# LKS_074DO_0329.net
KiCad netlist of a schematic drawn in Altium Designer
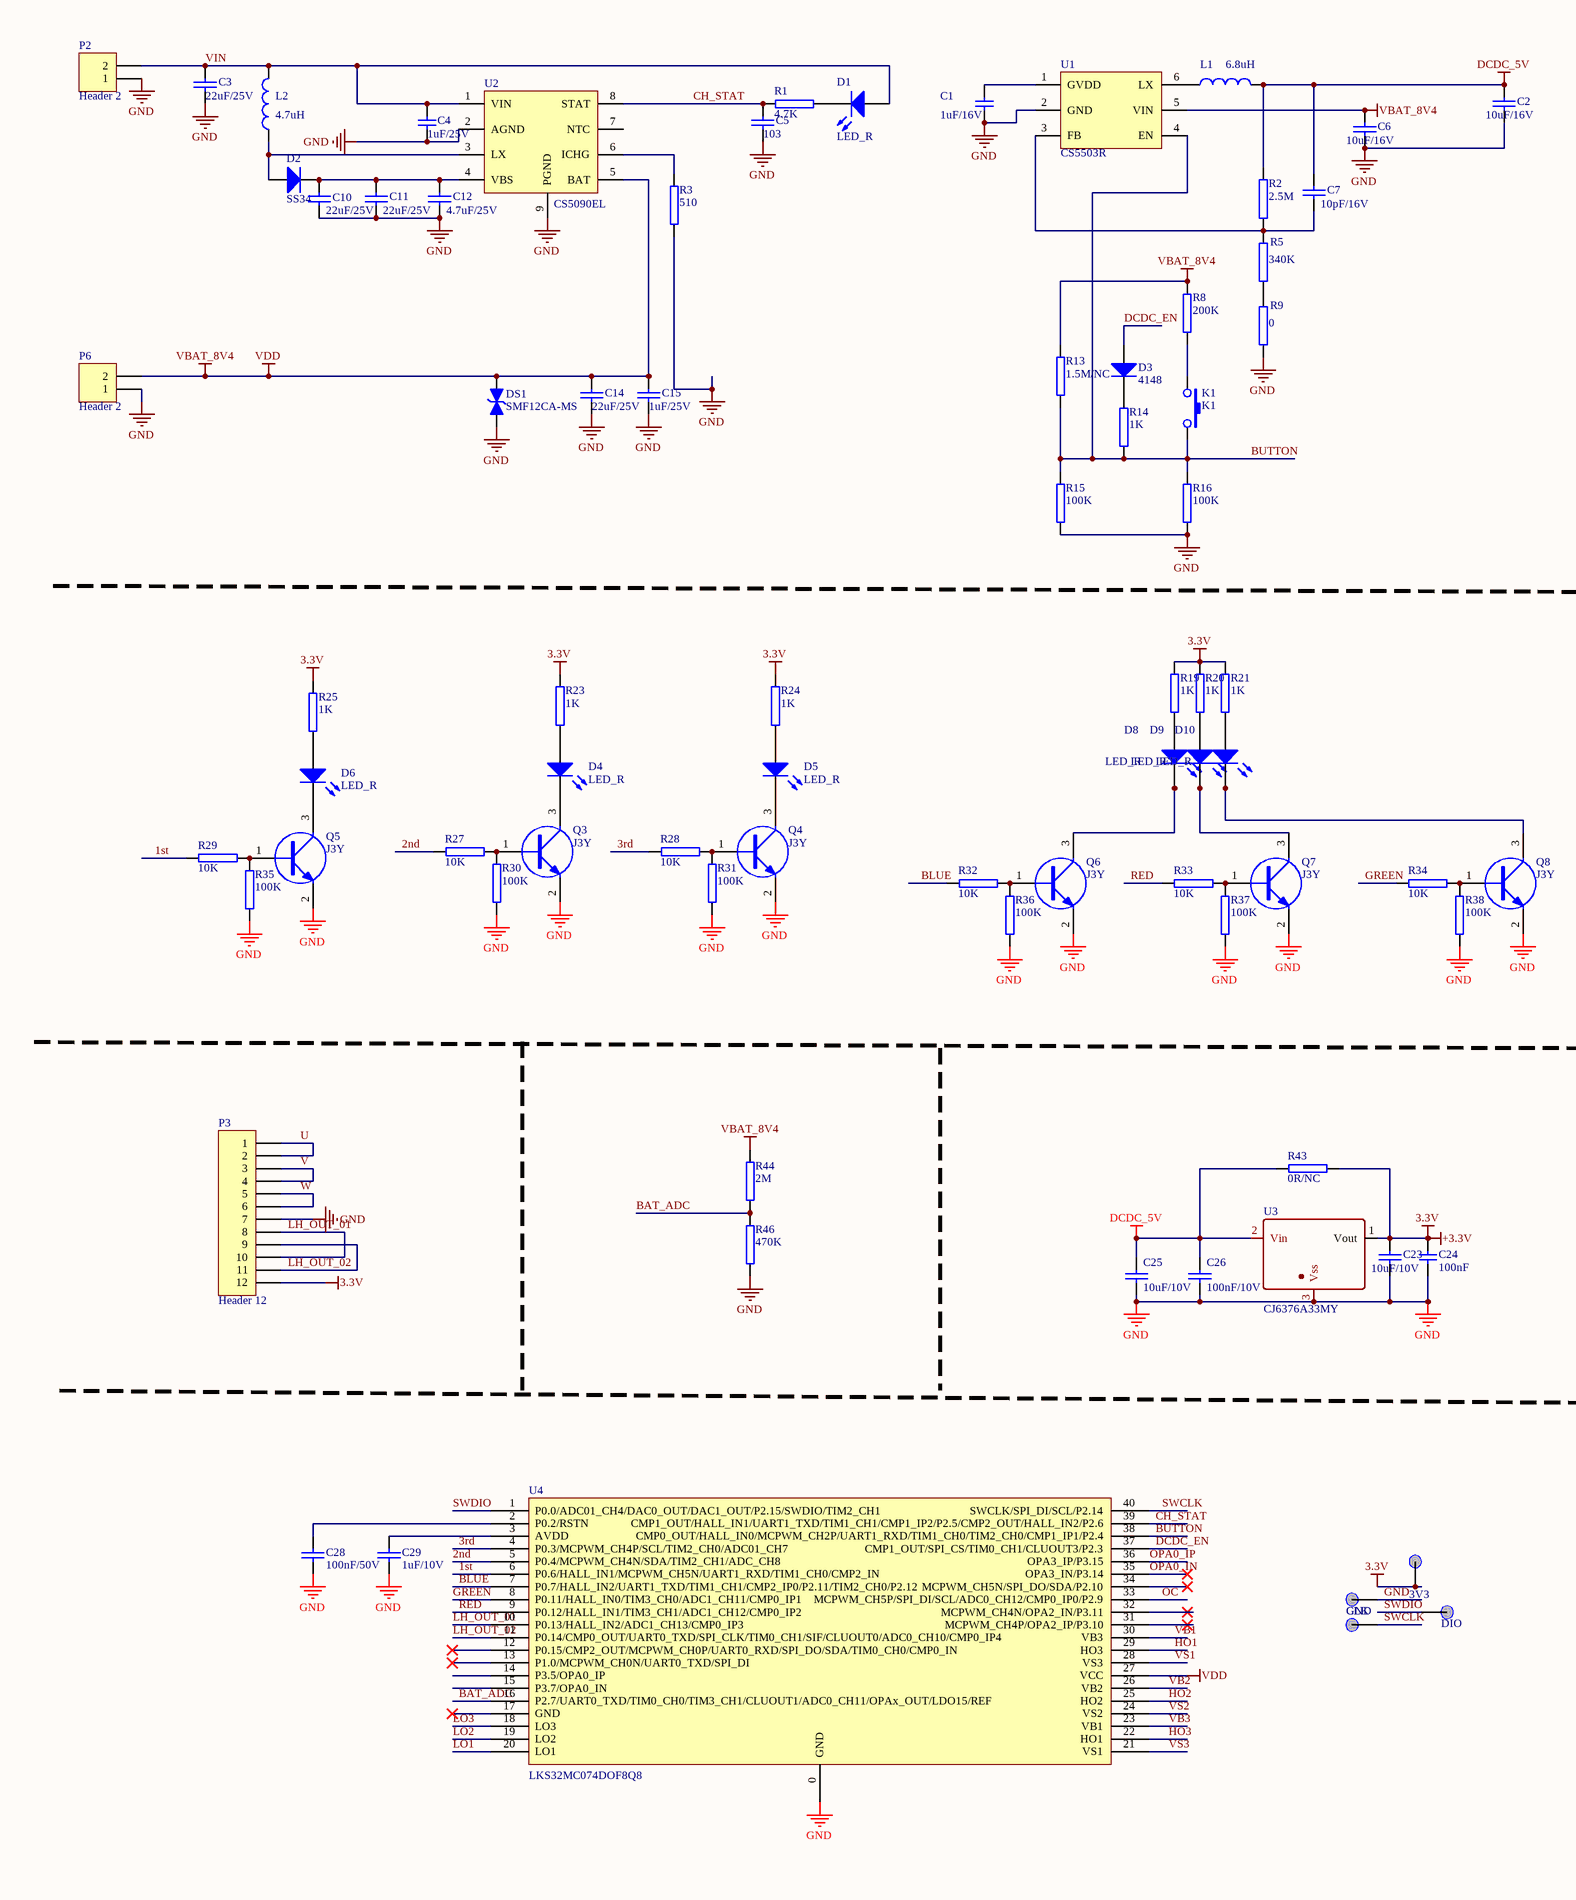
[diagram p0: LKS_074DO_0329.SchDoc, left]
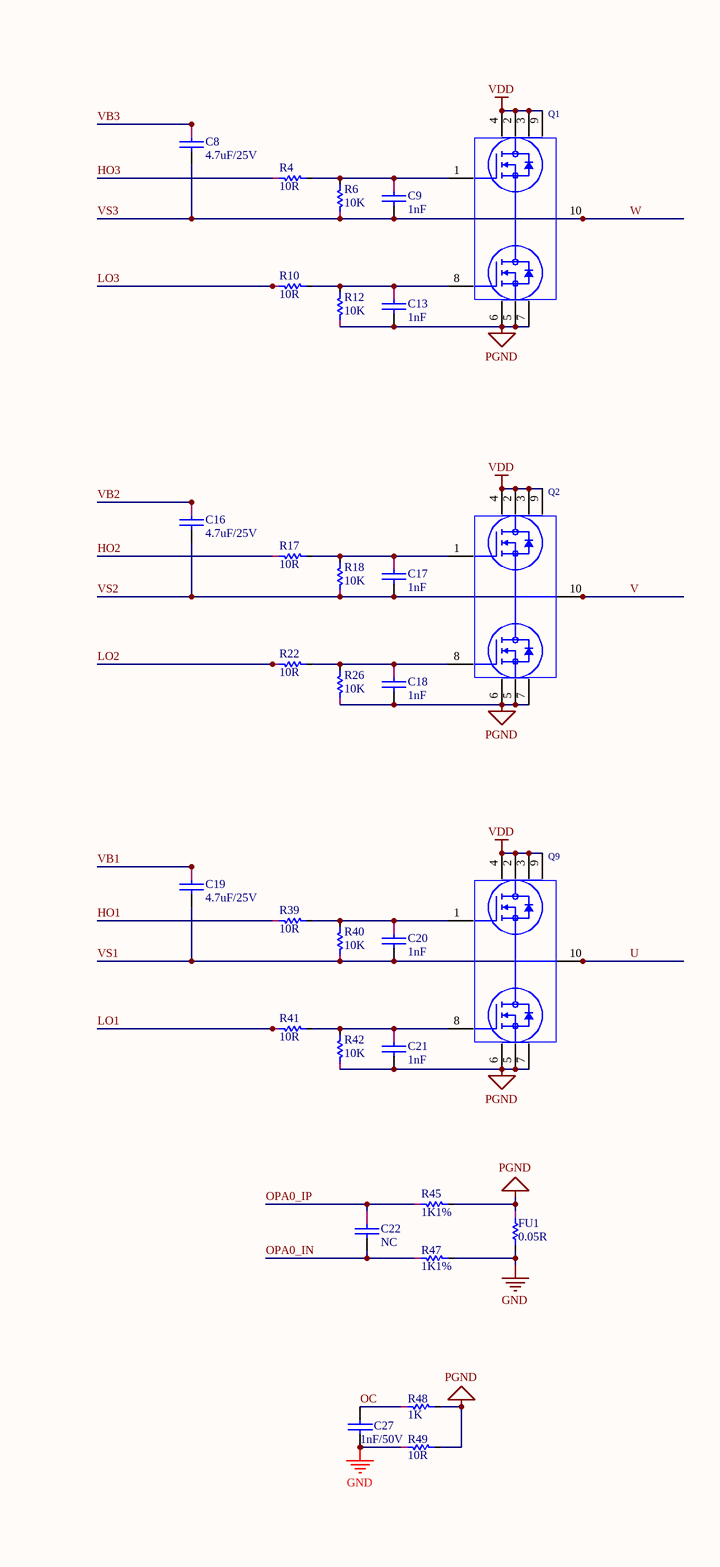
[diagram p1: LKS_074DO_0329.SchDoc, right]

(export (version "E")
  (design (tool "Eeschema 10.0.6"))
  (components
    (comp (ref "3V3") (value "test") (footprint "piot") (libsource (lib "LKS074DO_BRUSH_0329") (part "test")))
    (comp (ref "C1") (value "1uF/16V") (footprint "C 0402_M") (libsource (lib "") (part "CAP_2")))
    (comp (ref "C2")
      (value "10uF/16V")
      (footprint "C 0603_M")
      (description "Capacitor")
      (libsource (lib "*") (part "CAP"))
    )
    (comp (ref "C3")
      (value "22uF/25V")
      (footprint "C 0603_M")
      (description "Capacitor")
      (libsource (lib "*") (part "CAP"))
    )
    (comp (ref "C4") (value "1uF/25V") (footprint "C 0402_M") (libsource (lib "") (part "CAP_2")))
    (comp (ref "C5")
      (value "103")
      (footprint "R 0402_M")
      (description "Capacitor")
      (libsource (lib "*") (part "CAP"))
    )
    (comp (ref "C6")
      (value "10uF/16V")
      (footprint "C 0603_M")
      (description "Capacitor")
      (libsource (lib "*") (part "CAP"))
    )
    (comp (ref "C7")
      (value "10pF/16V")
      (footprint "C 0402_M")
      (description "Capacitor")
      (libsource (lib "*") (part "CAP"))
    )
    (comp (ref "C8")
      (value "4.7uF/25V")
      (footprint "C 0402_M")
      (description "Capacitor")
      (libsource (lib "") (part "CAP_1"))
    )
    (comp (ref "C9")
      (value "1nF")
      (footprint "C 0402_M")
      (description "Capacitor")
      (libsource (lib "") (part "CAP_1"))
    )
    (comp (ref "C10")
      (value "22uF/25V")
      (footprint "C 0603_M")
      (description "Capacitor")
      (libsource (lib "*") (part "CAP"))
    )
    (comp (ref "C11")
      (value "22uF/25V")
      (footprint "C 0603_M")
      (description "Capacitor")
      (libsource (lib "*") (part "CAP"))
    )
    (comp (ref "C12")
      (value "4.7uF/25V")
      (footprint "C 0402_M")
      (description "Capacitor")
      (libsource (lib "*") (part "CAP"))
    )
    (comp (ref "C13")
      (value "1nF")
      (footprint "C 0402_M")
      (description "Capacitor")
      (libsource (lib "") (part "CAP_1"))
    )
    (comp (ref "C14")
      (value "22uF/25V")
      (footprint "C 0603_M")
      (description "Capacitor")
      (libsource (lib "*") (part "CAP"))
    )
    (comp (ref "C15")
      (value "1uF/25V")
      (footprint "C 0402_M")
      (description "Capacitor")
      (libsource (lib "*") (part "CAP"))
    )
    (comp (ref "C16")
      (value "4.7uF/25V")
      (footprint "C 0402_M")
      (description "Capacitor")
      (libsource (lib "") (part "CAP_1"))
    )
    (comp (ref "C17")
      (value "1nF")
      (footprint "C 0402_M")
      (description "Capacitor")
      (libsource (lib "") (part "CAP_1"))
    )
    (comp (ref "C18")
      (value "1nF")
      (footprint "C 0402_M")
      (description "Capacitor")
      (libsource (lib "") (part "CAP_1"))
    )
    (comp (ref "C19")
      (value "4.7uF/25V")
      (footprint "C 0402_M")
      (description "Capacitor")
      (libsource (lib "") (part "CAP_1"))
    )
    (comp (ref "C20")
      (value "1nF")
      (footprint "C 0402_M")
      (description "Capacitor")
      (libsource (lib "") (part "CAP_1"))
    )
    (comp (ref "C21")
      (value "1nF")
      (footprint "C 0402_M")
      (description "Capacitor")
      (libsource (lib "") (part "CAP_1"))
    )
    (comp (ref "C22")
      (value "NC")
      (footprint "C 0402_M")
      (description "Capacitor")
      (libsource (lib "") (part "CAP_1"))
    )
    (comp (ref "C23")
      (value "10uF/10V")
      (footprint "C 0603_M")
      (description "Capacitor")
      (libsource (lib "*") (part "CAP"))
    )
    (comp (ref "C24") (value "100nF") (footprint "C 0402_M") (libsource (lib "") (part "CAP_2")))
    (comp (ref "C25")
      (value "10uF/10V")
      (footprint "C 0603_M")
      (description "Capacitor")
      (libsource (lib "*") (part "CAP"))
    )
    (comp (ref "C26")
      (value "100nF/10V")
      (footprint "C 0402_M")
      (description "Capacitor")
      (libsource (lib "*") (part "CAP"))
    )
    (comp (ref "C27")
      (value "1nF/50V")
      (footprint "C 0402_M")
      (description "Capacitor")
      (libsource (lib "*") (part "C"))
    )
    (comp (ref "C28")
      (value "100nF/50V")
      (footprint "C 0402_M")
      (description "Capacitor")
      (libsource (lib "*") (part "C"))
    )
    (comp (ref "C29")
      (value "1uF/10V")
      (footprint "C 0402_M")
      (description "Capacitor")
      (libsource (lib "*") (part "C"))
    )
    (comp (ref "CLK") (value "test") (footprint "piot") (libsource (lib "LKS074DO_BRUSH_0329") (part "test")))
    (comp (ref "D1") (value "LED_R") (footprint "0603-LED") (libsource (lib "PuXun1") (part "LED")))
    (comp (ref "D2")
      (value "SS34")
      (footprint "SOD123FL")
      (description "Default Diode")
      (fields (field (name "PUBLISHER") "Altium Limited"))
      (libsource (lib "LKS034DO_Motor_0520_1") (part "Diode"))
    )
    (comp (ref "D3")
      (value "4148")
      (footprint "SOD-323")
      (description "Default Diode")
      (fields (field (name "PUBLISHER") "Altium Limited"))
      (libsource (lib "LKS034DO_Motor_0520_1") (part "Diode"))
    )
    (comp (ref "D4") (value "LED_R") (footprint "0603-LED") (libsource (lib "PuXun1") (part "LED")))
    (comp (ref "D5") (value "LED_R") (footprint "0603-LED") (libsource (lib "PuXun1") (part "LED")))
    (comp (ref "D6") (value "LED_R") (footprint "0603-LED") (libsource (lib "PuXun1") (part "LED")))
    (comp (ref "D8") (value "LED_R") (footprint "0603-LED") (libsource (lib "PuXun1") (part "LED")))
    (comp (ref "D9") (value "LED_R") (footprint "0603-LED") (libsource (lib "PuXun1") (part "LED")))
    (comp (ref "D10") (value "LED_R") (footprint "0603-LED") (libsource (lib "PuXun1") (part "LED")))
    (comp (ref "DIO") (value "test") (footprint "piot") (libsource (lib "LKS074DO_BRUSH_0329") (part "test")))
    (comp (ref "DS1")
      (value "SMF12CA-MS")
      (footprint "SOD-123F")
      (description "12V/19.9V")
      (libsource (lib "*") (part "DIODE-3"))
    )
    (comp (ref "FU1") (value "0.05R") (footprint "R 0805_M") (libsource (lib "*") (part "RAS")))
    (comp (ref "GND") (value "test") (footprint "piot") (libsource (lib "LKS074DO_BRUSH_0329") (part "test")))
    (comp (ref "K1") (value "K1") (footprint "SMD3.3X3.3X2") (libsource (lib "SCHLIB_NEW") (part "K1")))
    (comp (ref "L1")
      (value "6.8uH")
      (footprint "SMD3.5X3 .2- duplicate")
      (description "Inductor")
      (fields (field (name "PUBLISHER") "Altium Limited"))
      (libsource (lib "Miscellaneous Devices") (part "Inductor"))
    )
    (comp (ref "L2")
      (value "4.7uH")
      (footprint "SMD3.5X3 .2- duplicate")
      (description "Inductor")
      (fields (field (name "PUBLISHER") "Altium Limited"))
      (libsource (lib "Miscellaneous Devices") (part "Inductor"))
    )
    (comp (ref "P2")
      (value "Header 2")
      (footprint "CONN_SMD_2P_0.6")
      (description "Header, 2-Pin")
      (fields (field (name "PUBLISHER") "Altium Limited"))
      (libsource (lib "Miscellaneous Connectors") (part "Header 2"))
    )
    (comp (ref "P3")
      (value "Header 12")
      (footprint "SMD-12")
      (description "Header, 12-Pin")
      (fields (field (name "PUBLISHER") "Altium Limited"))
      (libsource (lib "Miscellaneous Connectors") (part "Header 12"))
    )
    (comp (ref "P6")
      (value "Header 2")
      (footprint "CONN_SMD_2P_0.6")
      (description "Header, 2-Pin")
      (fields (field (name "PUBLISHER") "Altium Limited"))
      (libsource (lib "Miscellaneous Connectors") (part "Header 2"))
    )
    (comp (ref "Q1") (value "CJBM3020") (footprint "DFN-3X3_8") (libsource (lib "*") (part "CJBM3020")))
    (comp (ref "Q2") (value "CJBM3020") (footprint "DFN-3X3_8") (libsource (lib "*") (part "CJBM3020")))
    (comp (ref "Q3")
      (value "J3Y")
      (footprint "SOT-23")
      (description "NPN Transistor")
      (libsource (lib "*") (part "NPN"))
    )
    (comp (ref "Q4")
      (value "J3Y")
      (footprint "SOT-23")
      (description "NPN Transistor")
      (libsource (lib "*") (part "NPN"))
    )
    (comp (ref "Q5")
      (value "J3Y")
      (footprint "SOT-23")
      (description "NPN Transistor")
      (libsource (lib "*") (part "NPN"))
    )
    (comp (ref "Q6")
      (value "J3Y")
      (footprint "SOT-23")
      (description "NPN Transistor")
      (libsource (lib "*") (part "NPN"))
    )
    (comp (ref "Q7")
      (value "J3Y")
      (footprint "SOT-23")
      (description "NPN Transistor")
      (libsource (lib "*") (part "NPN"))
    )
    (comp (ref "Q8")
      (value "J3Y")
      (footprint "SOT-23")
      (description "NPN Transistor")
      (libsource (lib "*") (part "NPN"))
    )
    (comp (ref "Q9") (value "CJBM3020") (footprint "DFN-3X3_8") (libsource (lib "*") (part "CJBM3020")))
    (comp (ref "R1") (value "4.7K") (footprint "C 0402_M") (libsource (lib "*") (part "RES2_S")))
    (comp (ref "R2") (value "2.5M") (footprint "C 0402_M") (libsource (lib "*") (part "RES2_S")))
    (comp (ref "R3") (value "510") (footprint "R 0402_M") (libsource (lib "*") (part "RES2_S")))
    (comp (ref "R4") (value "10R") (footprint "R 0402_M") (libsource (lib "*") (part "RAS")))
    (comp (ref "R5") (value "340K") (footprint "C 0402_M") (libsource (lib "*") (part "RES2_S")))
    (comp (ref "R6") (value "10K") (footprint "R 0402_M") (libsource (lib "*") (part "RAS")))
    (comp (ref "R8") (value "200K") (footprint "C 0402_M") (libsource (lib "*") (part "RES2_S")))
    (comp (ref "R9") (value "0") (footprint "C 0402_M") (libsource (lib "*") (part "RES2_S")))
    (comp (ref "R10") (value "10R") (footprint "R 0402_M") (libsource (lib "*") (part "RAS")))
    (comp (ref "R12") (value "10K") (footprint "R 0402_M") (libsource (lib "*") (part "RAS")))
    (comp (ref "R13") (value "1.5M/NC") (footprint "C 0402_M") (libsource (lib "*") (part "RES2_S")))
    (comp (ref "R14") (value "1K") (footprint "C 0402_M") (libsource (lib "*") (part "RES2_S")))
    (comp (ref "R15") (value "100K") (footprint "C 0402_M") (libsource (lib "*") (part "RES2_S")))
    (comp (ref "R16") (value "100K") (footprint "C 0402_M") (libsource (lib "*") (part "RES2_S")))
    (comp (ref "R17") (value "10R") (footprint "R 0402_M") (libsource (lib "*") (part "RAS")))
    (comp (ref "R18") (value "10K") (footprint "R 0402_M") (libsource (lib "*") (part "RAS")))
    (comp (ref "R19") (value "1K") (footprint "C 0402_M") (libsource (lib "*") (part "RES2_S")))
    (comp (ref "R20") (value "1K") (footprint "C 0402_M") (libsource (lib "*") (part "RES2_S")))
    (comp (ref "R21") (value "1K") (footprint "C 0402_M") (libsource (lib "*") (part "RES2_S")))
    (comp (ref "R22") (value "10R") (footprint "R 0402_M") (libsource (lib "*") (part "RAS")))
    (comp (ref "R23") (value "1K") (footprint "C 0402_M") (libsource (lib "*") (part "RES2_S")))
    (comp (ref "R24") (value "1K") (footprint "C 0402_M") (libsource (lib "*") (part "RES2_S")))
    (comp (ref "R25") (value "1K") (footprint "C 0402_M") (libsource (lib "*") (part "RES2_S")))
    (comp (ref "R26") (value "10K") (footprint "R 0402_M") (libsource (lib "*") (part "RAS")))
    (comp (ref "R27") (value "10K") (footprint "C 0402_M") (libsource (lib "*") (part "RES2_S")))
    (comp (ref "R28") (value "10K") (footprint "C 0402_M") (libsource (lib "*") (part "RES2_S")))
    (comp (ref "R29") (value "10K") (footprint "C 0402_M") (libsource (lib "*") (part "RES2_S")))
    (comp (ref "R30") (value "100K") (footprint "C 0402_M") (libsource (lib "*") (part "RES2_S")))
    (comp (ref "R31") (value "100K") (footprint "C 0402_M") (libsource (lib "*") (part "RES2_S")))
    (comp (ref "R32") (value "10K") (footprint "C 0402_M") (libsource (lib "*") (part "RES2_S")))
    (comp (ref "R33") (value "10K") (footprint "C 0402_M") (libsource (lib "*") (part "RES2_S")))
    (comp (ref "R34") (value "10K") (footprint "C 0402_M") (libsource (lib "*") (part "RES2_S")))
    (comp (ref "R35") (value "100K") (footprint "C 0402_M") (libsource (lib "*") (part "RES2_S")))
    (comp (ref "R36") (value "100K") (footprint "C 0402_M") (libsource (lib "*") (part "RES2_S")))
    (comp (ref "R37") (value "100K") (footprint "C 0402_M") (libsource (lib "*") (part "RES2_S")))
    (comp (ref "R38") (value "100K") (footprint "C 0402_M") (libsource (lib "*") (part "RES2_S")))
    (comp (ref "R39") (value "10R") (footprint "R 0402_M") (libsource (lib "*") (part "RAS")))
    (comp (ref "R40") (value "10K") (footprint "R 0402_M") (libsource (lib "*") (part "RAS")))
    (comp (ref "R41") (value "10R") (footprint "R 0402_M") (libsource (lib "*") (part "RAS")))
    (comp (ref "R42") (value "10K") (footprint "R 0402_M") (libsource (lib "*") (part "RAS")))
    (comp (ref "R43") (value "0R/NC") (footprint "0603") (libsource (lib "*") (part "RES2_S")))
    (comp (ref "R44") (value "2M") (footprint "C 0402_M") (libsource (lib "*") (part "RES2_S")))
    (comp (ref "R45") (value "1K1%") (footprint "R 0402_M") (libsource (lib "*") (part "RAS")))
    (comp (ref "R46") (value "470K") (footprint "C 0402_M") (libsource (lib "*") (part "RES2_S")))
    (comp (ref "R47") (value "1K1%") (footprint "R 0402_M") (libsource (lib "*") (part "RAS")))
    (comp (ref "R48") (value "1K") (footprint "R 0402_M") (libsource (lib "*") (part "RAS")))
    (comp (ref "R49") (value "10R") (footprint "R 0402_M") (libsource (lib "*") (part "RAS")))
    (comp (ref "U1")
      (value "CS5503R")
      (footprint "SOT23-6L")
      (libsource (lib "LKS034DO_Motor_0520_1") (part "CS5503R"))
    )
    (comp (ref "U2")
      (value "CS5090EL")
      (footprint "DFN2X2_8_0.5")
      (libsource (lib "LKS034DO_Motor_0520_1") (part "CS5090EL"))
    )
    (comp (ref "U3")
      (value "CJ6376A33MY")
      (footprint "SOT-23")
      (libsource (lib "LKS034DO_Motor_0520_1") (part "78L15"))
    )
    (comp (ref "U4")
      (value "LKS32MC074DOF8Q8")
      (footprint "QFN40")
      (description "芯片")
      (libsource (lib "Q_LINKO_V1.0") (part "LKS32MC074DF8Q8"))
    )
  )
  (nets
    (net (code "1") (name "+3.3V") (class "Default")
      (node (ref "3V3") (pin "1") (pinfunction "1_1") (pintype "passive"))
      (node (ref "C23") (pin "2") (pinfunction "2_2") (pintype "passive"))
      (node (ref "C24") (pin "1") (pinfunction "1_1") (pintype "passive"))
      (node (ref "P3") (pin "12") (pinfunction "12_12") (pintype "passive"))
      (node (ref "R19") (pin "2") (pinfunction "2_2") (pintype "passive"))
      (node (ref "R20") (pin "2") (pinfunction "2_2") (pintype "passive"))
      (node (ref "R21") (pin "2") (pinfunction "2_2") (pintype "passive"))
      (node (ref "R23") (pin "2") (pinfunction "2_2") (pintype "passive"))
      (node (ref "R24") (pin "2") (pinfunction "2_2") (pintype "passive"))
      (node (ref "R25") (pin "2") (pinfunction "2_2") (pintype "passive"))
      (node (ref "R43") (pin "2") (pinfunction "2_2") (pintype "passive"))
      (node (ref "U3") (pin "1") (pinfunction "Vout_1") (pintype "passive"))
    )
    (net (code "2") (name "/1st") (class "Default")
      (node (ref "R29") (pin "2") (pinfunction "2_2") (pintype "passive"))
      (node (ref "U4") (pin "6") (pinfunction "P0.6/HALL_IN1/MCPWM_CH5N/UART1_RXD/TIM1_CH0/CMP2_IN_6") (pintype "passive"))
    )
    (net (code "3") (name "/2nd") (class "Default")
      (node (ref "R27") (pin "2") (pinfunction "2_2") (pintype "passive"))
      (node (ref "U4") (pin "5") (pinfunction "P0.4/MCPWM_CH4N/SDA/TIM2_CH1/ADC_CH8_5") (pintype "passive"))
    )
    (net (code "4") (name "/3rd") (class "Default")
      (node (ref "R28") (pin "2") (pinfunction "2_2") (pintype "passive"))
      (node (ref "U4") (pin "4") (pinfunction "P0.3/MCPWM_CH4P/SCL/TIM2_CH0/ADC01_CH7_4") (pintype "passive"))
    )
    (net (code "5") (name "/BAT_ADC") (class "Default")
      (node (ref "R44") (pin "2") (pinfunction "2_2") (pintype "passive"))
      (node (ref "R46") (pin "1") (pinfunction "1_1") (pintype "passive"))
      (node (ref "U4") (pin "16") (pinfunction "P2.7/UART0_TXD/TIM0_CH0/TIM3_CH1/CLUOUT1/ADC0_CH11/OPAx_OUT/LDO15/REF_16") (pintype "passive"))
    )
    (net (code "6") (name "/BLUE") (class "Default")
      (node (ref "R32") (pin "2") (pinfunction "2_2") (pintype "passive"))
      (node (ref "U4") (pin "7") (pinfunction "P0.7/HALL_IN2/UART1_TXD/TIM1_CH1/CMP2_IP0/P2.11/TIM2_CH0/P2.12_7") (pintype "passive"))
    )
    (net (code "7") (name "/BUTTON") (class "Default")
      (node (ref "K1") (pin "2") (pintype "passive"))
      (node (ref "R13") (pin "2") (pinfunction "2_2") (pintype "passive"))
      (node (ref "R14") (pin "2") (pinfunction "2_2") (pintype "passive"))
      (node (ref "R15") (pin "2") (pinfunction "2_2") (pintype "passive"))
      (node (ref "R16") (pin "1") (pinfunction "1_1") (pintype "passive"))
      (node (ref "U1") (pin "4") (pinfunction "EN_4") (pintype "passive"))
      (node (ref "U4") (pin "38") (pinfunction "CMP0_OUT/HALL_IN0/MCPWM_CH2P/UART1_RXD/TIM1_CH0/TIM2_CH0/CMP1_IP1/P2.4_38") (pintype "passive"))
    )
    (net (code "8") (name "/CH_STAT") (class "Default")
      (node (ref "C5") (pin "2") (pinfunction "2_2") (pintype "passive"))
      (node (ref "R1") (pin "1") (pinfunction "1_1") (pintype "passive"))
      (node (ref "U2") (pin "8") (pinfunction "STAT_8") (pintype "passive"))
      (node (ref "U4") (pin "39") (pinfunction "CMP1_OUT/HALL_IN1/UART1_TXD/TIM1_CH1/CMP1_IP2/P2.5/CMP2_OUT/HALL_IN2/P2.6_39") (pintype "passive"))
    )
    (net (code "9") (name "/DCDC_EN") (class "Default")
      (node (ref "D3") (pin "1") (pinfunction "A_1") (pintype "passive"))
      (node (ref "U4") (pin "37") (pinfunction "CMP1_OUT/SPI_CS/TIM0_CH1/CLUOUT3/P2.3_37") (pintype "passive"))
    )
    (net (code "10") (name "/GREEN") (class "Default")
      (node (ref "R34") (pin "2") (pinfunction "2_2") (pintype "passive"))
      (node (ref "U4") (pin "8") (pinfunction "P0.11/HALL_IN0/TIM3_CH0/ADC1_CH11/CMP0_IP1_8") (pintype "passive"))
    )
    (net (code "11") (name "/HO1") (class "Default")
      (node (ref "R39") (pin "2") (pinfunction "2_2") (pintype "passive"))
      (node (ref "U4") (pin "29") (pinfunction "HO3_29") (pintype "passive"))
    )
    (net (code "12") (name "/HO2") (class "Default")
      (node (ref "R17") (pin "2") (pinfunction "2_2") (pintype "passive"))
      (node (ref "U4") (pin "25") (pinfunction "HO2_25") (pintype "passive"))
    )
    (net (code "13") (name "/HO3") (class "Default")
      (node (ref "R4") (pin "2") (pinfunction "2_2") (pintype "passive"))
      (node (ref "U4") (pin "22") (pinfunction "HO1_22") (pintype "passive"))
    )
    (net (code "14") (name "/LH_OUT_01") (class "Default")
      (node (ref "P3") (pin "10") (pinfunction "10_10") (pintype "passive"))
      (node (ref "P3") (pin "8") (pinfunction "8_8") (pintype "passive"))
      (node (ref "U4") (pin "10") (pinfunction "P0.13/HALL_IN2/ADC1_CH13/CMP0_IP3_10") (pintype "passive"))
    )
    (net (code "15") (name "/LH_OUT_02") (class "Default")
      (node (ref "P3") (pin "11") (pinfunction "11_11") (pintype "passive"))
      (node (ref "P3") (pin "9") (pinfunction "9_9") (pintype "passive"))
      (node (ref "U4") (pin "11") (pinfunction "P0.14/CMP0_OUT/UART0_TXD/SPI_CLK/TIM0_CH1/SIF/CLUOUT0/ADC0_CH10/CMP0_IP4_11") (pintype "passive"))
    )
    (net (code "16") (name "/LO1") (class "Default")
      (node (ref "R41") (pin "2") (pinfunction "2_2") (pintype "passive"))
      (node (ref "U4") (pin "20") (pinfunction "LO1_20") (pintype "passive"))
    )
    (net (code "17") (name "/LO2") (class "Default")
      (node (ref "R22") (pin "2") (pinfunction "2_2") (pintype "passive"))
      (node (ref "U4") (pin "19") (pinfunction "LO2_19") (pintype "passive"))
    )
    (net (code "18") (name "/LO3") (class "Default")
      (node (ref "R10") (pin "2") (pinfunction "2_2") (pintype "passive"))
      (node (ref "U4") (pin "18") (pinfunction "LO3_18") (pintype "passive"))
    )
    (net (code "19") (name "/OC") (class "Default")
      (node (ref "C27") (pin "2") (pinfunction "2_2") (pintype "passive"))
      (node (ref "R48") (pin "2") (pinfunction "2_2") (pintype "passive"))
      (node (ref "U4") (pin "33") (pinfunction "MCPWM_CH5P/SPI_DI/SCL/ADC0_CH12/CMP0_IP0/P2.9_33") (pintype "passive"))
    )
    (net (code "20") (name "/OPA0_IN") (class "Default")
      (node (ref "C22") (pin "1") (pinfunction "1_1") (pintype "passive"))
      (node (ref "R47") (pin "2") (pinfunction "2_2") (pintype "passive"))
      (node (ref "U4") (pin "35") (pinfunction "OPA3_IN/P3.14_35") (pintype "passive"))
    )
    (net (code "21") (name "/OPA0_IP") (class "Default")
      (node (ref "C22") (pin "2") (pinfunction "2_2") (pintype "passive"))
      (node (ref "R45") (pin "2") (pinfunction "2_2") (pintype "passive"))
      (node (ref "U4") (pin "36") (pinfunction "OPA3_IP/P3.15_36") (pintype "passive"))
    )
    (net (code "22") (name "/RED") (class "Default")
      (node (ref "R33") (pin "2") (pinfunction "2_2") (pintype "passive"))
      (node (ref "U4") (pin "9") (pinfunction "P0.12/HALL_IN1/TIM3_CH1/ADC1_CH12/CMP0_IP2_9") (pintype "passive"))
    )
    (net (code "23") (name "/SWCLK") (class "Default")
      (node (ref "CLK") (pin "1") (pinfunction "1_1") (pintype "passive"))
      (node (ref "U4") (pin "40") (pinfunction "SWCLK/SPI_DI/SCL/P2.14_40") (pintype "passive"))
    )
    (net (code "24") (name "/SWDIO") (class "Default")
      (node (ref "DIO") (pin "1") (pinfunction "1_1") (pintype "passive"))
      (node (ref "U4") (pin "1") (pinfunction "P0.0/ADC01_CH4/DAC0_OUT/DAC1_OUT/P2.15/SWDIO/TIM2_CH1_1") (pintype "passive"))
    )
    (net (code "25") (name "/U") (class "Default")
      (node (ref "C19") (pin "1") (pinfunction "1_1") (pintype "passive"))
      (node (ref "C20") (pin "1") (pinfunction "1_1") (pintype "passive"))
      (node (ref "P3") (pin "1") (pinfunction "1_1") (pintype "passive"))
      (node (ref "P3") (pin "2") (pinfunction "2_2") (pintype "passive"))
      (node (ref "Q9") (pin "10") (pinfunction "S1/D2_10") (pintype "passive"))
      (node (ref "R40") (pin "2") (pinfunction "2_2") (pintype "passive"))
      (node (ref "U4") (pin "28") (pinfunction "VS3_28") (pintype "passive"))
    )
    (net (code "26") (name "/V") (class "Default")
      (node (ref "C16") (pin "1") (pinfunction "1_1") (pintype "passive"))
      (node (ref "C17") (pin "1") (pinfunction "1_1") (pintype "passive"))
      (node (ref "P3") (pin "3") (pinfunction "3_3") (pintype "passive"))
      (node (ref "P3") (pin "4") (pinfunction "4_4") (pintype "passive"))
      (node (ref "Q2") (pin "10") (pinfunction "S1/D2_10") (pintype "passive"))
      (node (ref "R18") (pin "2") (pinfunction "2_2") (pintype "passive"))
      (node (ref "U4") (pin "24") (pinfunction "VS2_24") (pintype "passive"))
    )
    (net (code "27") (name "/VB1") (class "Default")
      (node (ref "C19") (pin "2") (pinfunction "2_2") (pintype "passive"))
      (node (ref "U4") (pin "30") (pinfunction "VB3_30") (pintype "passive"))
    )
    (net (code "28") (name "/VB2") (class "Default")
      (node (ref "C16") (pin "2") (pinfunction "2_2") (pintype "passive"))
      (node (ref "U4") (pin "26") (pinfunction "VB2_26") (pintype "passive"))
    )
    (net (code "29") (name "/VB3") (class "Default")
      (node (ref "C8") (pin "2") (pinfunction "2_2") (pintype "passive"))
      (node (ref "U4") (pin "23") (pinfunction "VB1_23") (pintype "passive"))
    )
    (net (code "30") (name "/VIN") (class "Default")
      (node (ref "C3") (pin "2") (pinfunction "2_2") (pintype "passive"))
      (node (ref "C4") (pin "1") (pinfunction "1_1") (pintype "passive"))
      (node (ref "D1") (pin "1") (pinfunction "A_1") (pintype "passive"))
      (node (ref "L2") (pin "2") (pinfunction "2_2") (pintype "passive"))
      (node (ref "P2") (pin "2") (pinfunction "2_2") (pintype "passive"))
      (node (ref "U2") (pin "1") (pinfunction "VIN_1") (pintype "passive"))
    )
    (net (code "31") (name "/VS3") (class "Default")
      (node (ref "C8") (pin "1") (pinfunction "1_1") (pintype "passive"))
      (node (ref "C9") (pin "1") (pinfunction "1_1") (pintype "passive"))
      (node (ref "P3") (pin "5") (pinfunction "5_5") (pintype "passive"))
      (node (ref "P3") (pin "6") (pinfunction "6_6") (pintype "passive"))
      (node (ref "Q1") (pin "10") (pinfunction "S1/D2_10") (pintype "passive"))
      (node (ref "R6") (pin "2") (pinfunction "2_2") (pintype "passive"))
      (node (ref "U4") (pin "21") (pinfunction "VS1_21") (pintype "passive"))
    )
    (net (code "32") (name "DCDC_5V") (class "Default")
      (node (ref "C2") (pin "2") (pinfunction "2_2") (pintype "passive"))
      (node (ref "C25") (pin "2") (pinfunction "2_2") (pintype "passive"))
      (node (ref "C26") (pin "1") (pinfunction "1_1") (pintype "passive"))
      (node (ref "C7") (pin "2") (pinfunction "2_2") (pintype "passive"))
      (node (ref "L1") (pin "2") (pinfunction "2_2") (pintype "passive"))
      (node (ref "R2") (pin "1") (pinfunction "1_1") (pintype "passive"))
      (node (ref "R43") (pin "1") (pinfunction "1_1") (pintype "passive"))
      (node (ref "U3") (pin "2") (pinfunction "Vin_2") (pintype "passive"))
    )
    (net (code "33") (name "GND") (class "Default")
      (node (ref "C1") (pin "1") (pinfunction "1_1") (pintype "passive"))
      (node (ref "C10") (pin "1") (pinfunction "1_1") (pintype "passive"))
      (node (ref "C11") (pin "1") (pinfunction "1_1") (pintype "passive"))
      (node (ref "C12") (pin "1") (pinfunction "1_1") (pintype "passive"))
      (node (ref "C14") (pin "1") (pinfunction "1_1") (pintype "passive"))
      (node (ref "C15") (pin "1") (pinfunction "1_1") (pintype "passive"))
      (node (ref "C2") (pin "1") (pinfunction "1_1") (pintype "passive"))
      (node (ref "C23") (pin "1") (pinfunction "1_1") (pintype "passive"))
      (node (ref "C24") (pin "2") (pinfunction "2_2") (pintype "passive"))
      (node (ref "C25") (pin "1") (pinfunction "1_1") (pintype "passive"))
      (node (ref "C26") (pin "2") (pinfunction "2_2") (pintype "passive"))
      (node (ref "C27") (pin "1") (pinfunction "1_1") (pintype "passive"))
      (node (ref "C28") (pin "2") (pinfunction "2_2") (pintype "passive"))
      (node (ref "C29") (pin "1") (pinfunction "1_1") (pintype "passive"))
      (node (ref "C3") (pin "1") (pinfunction "1_1") (pintype "passive"))
      (node (ref "C4") (pin "2") (pinfunction "2_2") (pintype "passive"))
      (node (ref "C5") (pin "1") (pinfunction "1_1") (pintype "passive"))
      (node (ref "C6") (pin "1") (pinfunction "1_1") (pintype "passive"))
      (node (ref "DS1") (pin "2") (pinfunction "K_2") (pintype "passive"))
      (node (ref "FU1") (pin "1") (pinfunction "1_1") (pintype "passive"))
      (node (ref "GND") (pin "1") (pinfunction "1_1") (pintype "passive"))
      (node (ref "P2") (pin "1") (pinfunction "1_1") (pintype "passive"))
      (node (ref "P3") (pin "7") (pinfunction "7_7") (pintype "passive"))
      (node (ref "P6") (pin "1") (pinfunction "1_1") (pintype "passive"))
      (node (ref "Q3") (pin "2") (pinfunction "E_2") (pintype "passive"))
      (node (ref "Q4") (pin "2") (pinfunction "E_2") (pintype "passive"))
      (node (ref "Q5") (pin "2") (pinfunction "E_2") (pintype "passive"))
      (node (ref "Q6") (pin "2") (pinfunction "E_2") (pintype "passive"))
      (node (ref "Q7") (pin "2") (pinfunction "E_2") (pintype "passive"))
      (node (ref "Q8") (pin "2") (pinfunction "E_2") (pintype "passive"))
      (node (ref "R15") (pin "1") (pinfunction "1_1") (pintype "passive"))
      (node (ref "R16") (pin "2") (pinfunction "2_2") (pintype "passive"))
      (node (ref "R3") (pin "2") (pinfunction "2_2") (pintype "passive"))
      (node (ref "R30") (pin "2") (pinfunction "2_2") (pintype "passive"))
      (node (ref "R31") (pin "2") (pinfunction "2_2") (pintype "passive"))
      (node (ref "R35") (pin "2") (pinfunction "2_2") (pintype "passive"))
      (node (ref "R36") (pin "2") (pinfunction "2_2") (pintype "passive"))
      (node (ref "R37") (pin "2") (pinfunction "2_2") (pintype "passive"))
      (node (ref "R38") (pin "2") (pinfunction "2_2") (pintype "passive"))
      (node (ref "R46") (pin "2") (pinfunction "2_2") (pintype "passive"))
      (node (ref "R47") (pin "1") (pinfunction "1_1") (pintype "passive"))
      (node (ref "R49") (pin "2") (pinfunction "2_2") (pintype "passive"))
      (node (ref "R9") (pin "2") (pinfunction "2_2") (pintype "passive"))
      (node (ref "U1") (pin "2") (pinfunction "GND_2") (pintype "passive"))
      (node (ref "U2") (pin "2") (pinfunction "AGND_2") (pintype "passive"))
      (node (ref "U2") (pin "9") (pinfunction "PGND_9") (pintype "passive"))
      (node (ref "U3") (pin "3") (pinfunction "Vss_3") (pintype "passive"))
      (node (ref "U4") (pin "0") (pinfunction "GND_0") (pintype "passive"))
    )
    (net (code "34") (name "Net-(D1-K)") (class "Default")
      (node (ref "D1") (pin "2") (pinfunction "K_2") (pintype "passive"))
      (node (ref "R1") (pin "2") (pinfunction "2_2") (pintype "passive"))
    )
    (net (code "35") (name "Net-(D2-A)") (class "Default")
      (node (ref "D2") (pin "1") (pinfunction "A_1") (pintype "passive"))
      (node (ref "L2") (pin "1") (pinfunction "1_1") (pintype "passive"))
      (node (ref "U2") (pin "3") (pinfunction "LX_3") (pintype "passive"))
    )
    (net (code "36") (name "Net-(D2-K)") (class "Default")
      (node (ref "C10") (pin "2") (pinfunction "2_2") (pintype "passive"))
      (node (ref "C11") (pin "2") (pinfunction "2_2") (pintype "passive"))
      (node (ref "C12") (pin "2") (pinfunction "2_2") (pintype "passive"))
      (node (ref "D2") (pin "2") (pinfunction "K_2") (pintype "passive"))
      (node (ref "U2") (pin "4") (pinfunction "VBS_4") (pintype "passive"))
    )
    (net (code "37") (name "Net-(D3-K)") (class "Default")
      (node (ref "D3") (pin "2") (pinfunction "K_2") (pintype "passive"))
      (node (ref "R14") (pin "1") (pinfunction "1_1") (pintype "passive"))
    )
    (net (code "38") (name "Net-(D4-A)") (class "Default")
      (node (ref "D4") (pin "1") (pinfunction "A_1") (pintype "passive"))
      (node (ref "R23") (pin "1") (pinfunction "1_1") (pintype "passive"))
    )
    (net (code "39") (name "Net-(D4-K)") (class "Default")
      (node (ref "D4") (pin "2") (pinfunction "K_2") (pintype "passive"))
      (node (ref "Q3") (pin "3") (pinfunction "C_3") (pintype "passive"))
    )
    (net (code "40") (name "Net-(D5-A)") (class "Default")
      (node (ref "D5") (pin "1") (pinfunction "A_1") (pintype "passive"))
      (node (ref "R24") (pin "1") (pinfunction "1_1") (pintype "passive"))
    )
    (net (code "41") (name "Net-(D5-K)") (class "Default")
      (node (ref "D5") (pin "2") (pinfunction "K_2") (pintype "passive"))
      (node (ref "Q4") (pin "3") (pinfunction "C_3") (pintype "passive"))
    )
    (net (code "42") (name "Net-(D6-A)") (class "Default")
      (node (ref "D6") (pin "1") (pinfunction "A_1") (pintype "passive"))
      (node (ref "R25") (pin "1") (pinfunction "1_1") (pintype "passive"))
    )
    (net (code "43") (name "Net-(D6-K)") (class "Default")
      (node (ref "D6") (pin "2") (pinfunction "K_2") (pintype "passive"))
      (node (ref "Q5") (pin "3") (pinfunction "C_3") (pintype "passive"))
    )
    (net (code "44") (name "Net-(D8-A)") (class "Default")
      (node (ref "D8") (pin "1") (pinfunction "A_1") (pintype "passive"))
      (node (ref "R19") (pin "1") (pinfunction "1_1") (pintype "passive"))
    )
    (net (code "45") (name "Net-(D8-K)") (class "Default")
      (node (ref "D8") (pin "2") (pinfunction "K_2") (pintype "passive"))
      (node (ref "Q6") (pin "3") (pinfunction "C_3") (pintype "passive"))
    )
    (net (code "46") (name "Net-(D9-A)") (class "Default")
      (node (ref "D9") (pin "1") (pinfunction "A_1") (pintype "passive"))
      (node (ref "R20") (pin "1") (pinfunction "1_1") (pintype "passive"))
    )
    (net (code "47") (name "Net-(D9-K)") (class "Default")
      (node (ref "D9") (pin "2") (pinfunction "K_2") (pintype "passive"))
      (node (ref "Q7") (pin "3") (pinfunction "C_3") (pintype "passive"))
    )
    (net (code "48") (name "Net-(D10-A)") (class "Default")
      (node (ref "D10") (pin "1") (pinfunction "A_1") (pintype "passive"))
      (node (ref "R21") (pin "1") (pinfunction "1_1") (pintype "passive"))
    )
    (net (code "49") (name "Net-(D10-K)") (class "Default")
      (node (ref "D10") (pin "2") (pinfunction "K_2") (pintype "passive"))
      (node (ref "Q8") (pin "3") (pinfunction "C_3") (pintype "passive"))
    )
    (net (code "50") (name "Net-(K1-Pad1)") (class "Default")
      (node (ref "K1") (pin "1") (pintype "passive"))
      (node (ref "R8") (pin "1") (pinfunction "1_1") (pintype "passive"))
    )
    (net (code "51") (name "Net-(Q1-G1)") (class "Default")
      (node (ref "C9") (pin "2") (pinfunction "2_2") (pintype "passive"))
      (node (ref "Q1") (pin "1") (pinfunction "G1_1") (pintype "passive"))
      (node (ref "R4") (pin "1") (pinfunction "1_1") (pintype "passive"))
      (node (ref "R6") (pin "1") (pinfunction "1_1") (pintype "passive"))
    )
    (net (code "52") (name "Net-(Q1-G2)") (class "Default")
      (node (ref "C13") (pin "2") (pinfunction "2_2") (pintype "passive"))
      (node (ref "Q1") (pin "8") (pinfunction "G2_8") (pintype "passive"))
      (node (ref "R10") (pin "1") (pinfunction "1_1") (pintype "passive"))
      (node (ref "R12") (pin "1") (pinfunction "1_1") (pintype "passive"))
    )
    (net (code "53") (name "Net-(Q2-G1)") (class "Default")
      (node (ref "C17") (pin "2") (pinfunction "2_2") (pintype "passive"))
      (node (ref "Q2") (pin "1") (pinfunction "G1_1") (pintype "passive"))
      (node (ref "R17") (pin "1") (pinfunction "1_1") (pintype "passive"))
      (node (ref "R18") (pin "1") (pinfunction "1_1") (pintype "passive"))
    )
    (net (code "54") (name "Net-(Q2-G2)") (class "Default")
      (node (ref "C18") (pin "2") (pinfunction "2_2") (pintype "passive"))
      (node (ref "Q2") (pin "8") (pinfunction "G2_8") (pintype "passive"))
      (node (ref "R22") (pin "1") (pinfunction "1_1") (pintype "passive"))
      (node (ref "R26") (pin "1") (pinfunction "1_1") (pintype "passive"))
    )
    (net (code "55") (name "Net-(Q3-B)") (class "Default")
      (node (ref "Q3") (pin "1") (pinfunction "B_1") (pintype "passive"))
      (node (ref "R27") (pin "1") (pinfunction "1_1") (pintype "passive"))
      (node (ref "R30") (pin "1") (pinfunction "1_1") (pintype "passive"))
    )
    (net (code "56") (name "Net-(Q4-B)") (class "Default")
      (node (ref "Q4") (pin "1") (pinfunction "B_1") (pintype "passive"))
      (node (ref "R28") (pin "1") (pinfunction "1_1") (pintype "passive"))
      (node (ref "R31") (pin "1") (pinfunction "1_1") (pintype "passive"))
    )
    (net (code "57") (name "Net-(Q5-B)") (class "Default")
      (node (ref "Q5") (pin "1") (pinfunction "B_1") (pintype "passive"))
      (node (ref "R29") (pin "1") (pinfunction "1_1") (pintype "passive"))
      (node (ref "R35") (pin "1") (pinfunction "1_1") (pintype "passive"))
    )
    (net (code "58") (name "Net-(Q6-B)") (class "Default")
      (node (ref "Q6") (pin "1") (pinfunction "B_1") (pintype "passive"))
      (node (ref "R32") (pin "1") (pinfunction "1_1") (pintype "passive"))
      (node (ref "R36") (pin "1") (pinfunction "1_1") (pintype "passive"))
    )
    (net (code "59") (name "Net-(Q7-B)") (class "Default")
      (node (ref "Q7") (pin "1") (pinfunction "B_1") (pintype "passive"))
      (node (ref "R33") (pin "1") (pinfunction "1_1") (pintype "passive"))
      (node (ref "R37") (pin "1") (pinfunction "1_1") (pintype "passive"))
    )
    (net (code "60") (name "Net-(Q8-B)") (class "Default")
      (node (ref "Q8") (pin "1") (pinfunction "B_1") (pintype "passive"))
      (node (ref "R34") (pin "1") (pinfunction "1_1") (pintype "passive"))
      (node (ref "R38") (pin "1") (pinfunction "1_1") (pintype "passive"))
    )
    (net (code "61") (name "Net-(Q9-G1)") (class "Default")
      (node (ref "C20") (pin "2") (pinfunction "2_2") (pintype "passive"))
      (node (ref "Q9") (pin "1") (pinfunction "G1_1") (pintype "passive"))
      (node (ref "R39") (pin "1") (pinfunction "1_1") (pintype "passive"))
      (node (ref "R40") (pin "1") (pinfunction "1_1") (pintype "passive"))
    )
    (net (code "62") (name "Net-(Q9-G2)") (class "Default")
      (node (ref "C21") (pin "2") (pinfunction "2_2") (pintype "passive"))
      (node (ref "Q9") (pin "8") (pinfunction "G2_8") (pintype "passive"))
      (node (ref "R41") (pin "1") (pinfunction "1_1") (pintype "passive"))
      (node (ref "R42") (pin "1") (pinfunction "1_1") (pintype "passive"))
    )
    (net (code "63") (name "Net-(R5-Pad2)") (class "Default")
      (node (ref "R5") (pin "2") (pinfunction "2_2") (pintype "passive"))
      (node (ref "R9") (pin "1") (pinfunction "1_1") (pintype "passive"))
    )
    (net (code "64") (name "Net-(U1-FB)") (class "Default")
      (node (ref "C7") (pin "1") (pinfunction "1_1") (pintype "passive"))
      (node (ref "R2") (pin "2") (pinfunction "2_2") (pintype "passive"))
      (node (ref "R5") (pin "1") (pinfunction "1_1") (pintype "passive"))
      (node (ref "U1") (pin "3") (pinfunction "FB_3") (pintype "passive"))
    )
    (net (code "65") (name "Net-(U1-GVDD)") (class "Default")
      (node (ref "C1") (pin "2") (pinfunction "2_2") (pintype "passive"))
      (node (ref "U1") (pin "1") (pinfunction "GVDD_1") (pintype "passive"))
    )
    (net (code "66") (name "Net-(U1-LX)") (class "Default")
      (node (ref "L1") (pin "1") (pinfunction "1_1") (pintype "passive"))
      (node (ref "U1") (pin "6") (pinfunction "LX_6") (pintype "passive"))
    )
    (net (code "67") (name "Net-(U2-ICHG)") (class "Default")
      (node (ref "R3") (pin "1") (pinfunction "1_1") (pintype "passive"))
      (node (ref "U2") (pin "6") (pinfunction "ICHG_6") (pintype "passive"))
    )
    (net (code "68") (name "Net-(U4-AVDD)") (class "Default")
      (node (ref "C29") (pin "2") (pinfunction "2_2") (pintype "passive"))
      (node (ref "U4") (pin "3") (pinfunction "AVDD_3") (pintype "passive"))
    )
    (net (code "69") (name "Net-(U4-P0.2{slash}RSTN)") (class "Default")
      (node (ref "C28") (pin "1") (pinfunction "1_1") (pintype "passive"))
      (node (ref "U4") (pin "2") (pinfunction "P0.2/RSTN_2") (pintype "passive"))
    )
    (net (code "70") (name "PGND") (class "Default")
      (node (ref "C13") (pin "1") (pinfunction "1_1") (pintype "passive"))
      (node (ref "C18") (pin "1") (pinfunction "1_1") (pintype "passive"))
      (node (ref "C21") (pin "1") (pinfunction "1_1") (pintype "passive"))
      (node (ref "FU1") (pin "2") (pinfunction "2_2") (pintype "passive"))
      (node (ref "Q1") (pin "5") (pinfunction "S2_5") (pintype "passive"))
      (node (ref "Q1") (pin "6") (pinfunction "S2_6") (pintype "passive"))
      (node (ref "Q1") (pin "7") (pinfunction "S2_7") (pintype "passive"))
      (node (ref "Q2") (pin "5") (pinfunction "S2_5") (pintype "passive"))
      (node (ref "Q2") (pin "6") (pinfunction "S2_6") (pintype "passive"))
      (node (ref "Q2") (pin "7") (pinfunction "S2_7") (pintype "passive"))
      (node (ref "Q9") (pin "5") (pinfunction "S2_5") (pintype "passive"))
      (node (ref "Q9") (pin "6") (pinfunction "S2_6") (pintype "passive"))
      (node (ref "Q9") (pin "7") (pinfunction "S2_7") (pintype "passive"))
      (node (ref "R12") (pin "2") (pinfunction "2_2") (pintype "passive"))
      (node (ref "R26") (pin "2") (pinfunction "2_2") (pintype "passive"))
      (node (ref "R42") (pin "2") (pinfunction "2_2") (pintype "passive"))
      (node (ref "R45") (pin "1") (pinfunction "1_1") (pintype "passive"))
      (node (ref "R48") (pin "1") (pinfunction "1_1") (pintype "passive"))
      (node (ref "R49") (pin "1") (pinfunction "1_1") (pintype "passive"))
    )
    (net (code "71") (name "VBAT_8V4") (class "Default")
      (node (ref "C14") (pin "2") (pinfunction "2_2") (pintype "passive"))
      (node (ref "C15") (pin "2") (pinfunction "2_2") (pintype "passive"))
      (node (ref "C6") (pin "2") (pinfunction "2_2") (pintype "passive"))
      (node (ref "DS1") (pin "1") (pinfunction "A_1") (pintype "passive"))
      (node (ref "P6") (pin "2") (pinfunction "2_2") (pintype "passive"))
      (node (ref "Q1") (pin "2") (pinfunction "D1_2") (pintype "passive"))
      (node (ref "Q1") (pin "3") (pinfunction "D1_3") (pintype "passive"))
      (node (ref "Q1") (pin "4") (pinfunction "D1_4") (pintype "passive"))
      (node (ref "Q1") (pin "9") (pinfunction "D1_9") (pintype "passive"))
      (node (ref "Q2") (pin "2") (pinfunction "D1_2") (pintype "passive"))
      (node (ref "Q2") (pin "3") (pinfunction "D1_3") (pintype "passive"))
      (node (ref "Q2") (pin "4") (pinfunction "D1_4") (pintype "passive"))
      (node (ref "Q2") (pin "9") (pinfunction "D1_9") (pintype "passive"))
      (node (ref "Q9") (pin "2") (pinfunction "D1_2") (pintype "passive"))
      (node (ref "Q9") (pin "3") (pinfunction "D1_3") (pintype "passive"))
      (node (ref "Q9") (pin "4") (pinfunction "D1_4") (pintype "passive"))
      (node (ref "Q9") (pin "9") (pinfunction "D1_9") (pintype "passive"))
      (node (ref "R13") (pin "1") (pinfunction "1_1") (pintype "passive"))
      (node (ref "R44") (pin "1") (pinfunction "1_1") (pintype "passive"))
      (node (ref "R8") (pin "2") (pinfunction "2_2") (pintype "passive"))
      (node (ref "U1") (pin "5") (pinfunction "VIN_5") (pintype "passive"))
      (node (ref "U2") (pin "5") (pinfunction "BAT_5") (pintype "passive"))
      (node (ref "U4") (pin "27") (pinfunction "VCC_27") (pintype "passive"))
    )
    (net (code "72") (name "unconnected-(U2-NTC-Pad7)") (class "Default")
      (node (ref "U2") (pin "7") (pinfunction "NTC_7") (pintype "passive"))
    )
    (net (code "73") (name "unconnected-(U4-GND-Pad17)") (class "Default")
      (node (ref "U4") (pin "17") (pinfunction "GND_17") (pintype "passive+no_connect"))
    )
    (net (code "74") (name "unconnected-(U4-MCPWM_CH4N{slash}OPA2_IN{slash}P3.11-Pad32)") (class "Default")
      (node (ref "U4") (pin "32") (pinfunction "MCPWM_CH4N/OPA2_IN/P3.11_32") (pintype "passive"))
    )
    (net (code "75") (name "unconnected-(U4-MCPWM_CH4P{slash}OPA2_IP{slash}P3.10-Pad31)") (class "Default")
      (node (ref "U4") (pin "31") (pinfunction "MCPWM_CH4P/OPA2_IP/P3.10_31") (pintype "passive"))
    )
    (net (code "76") (name "unconnected-(U4-MCPWM_CH5N{slash}SPI_DO{slash}SDA{slash}P2.10-Pad34)") (class "Default")
      (node (ref "U4") (pin "34") (pinfunction "MCPWM_CH5N/SPI_DO/SDA/P2.10_34") (pintype "passive+no_connect"))
    )
    (net (code "77") (name "unconnected-(U4-P0.15{slash}CMP2_OUT{slash}MCPWM_CH0P{slash}UART0_RXD{slash}SPI_DO{slash}SDA{slash}TIM0_CH0{slash}CMP0_IN-Pad12)") (class "Default")
      (node (ref "U4") (pin "12") (pinfunction "P0.15/CMP2_OUT/MCPWM_CH0P/UART0_RXD/SPI_DO/SDA/TIM0_CH0/CMP0_IN_12") (pintype "passive+no_connect"))
    )
    (net (code "78") (name "unconnected-(U4-P1.0{slash}MCPWM_CH0N{slash}UART0_TXD{slash}SPI_DI-Pad13)") (class "Default")
      (node (ref "U4") (pin "13") (pinfunction "P1.0/MCPWM_CH0N/UART0_TXD/SPI_DI_13") (pintype "passive+no_connect"))
    )
    (net (code "79") (name "unconnected-(U4-P3.5{slash}OPA0_IP-Pad14)") (class "Default")
      (node (ref "U4") (pin "14") (pinfunction "P3.5/OPA0_IP_14") (pintype "passive"))
    )
    (net (code "80") (name "unconnected-(U4-P3.7{slash}OPA0_IN-Pad15)") (class "Default")
      (node (ref "U4") (pin "15") (pinfunction "P3.7/OPA0_IN_15") (pintype "passive"))
    )
  )
)
